# schem.net
KiCad netlist of a schematic drawn in EAGLE
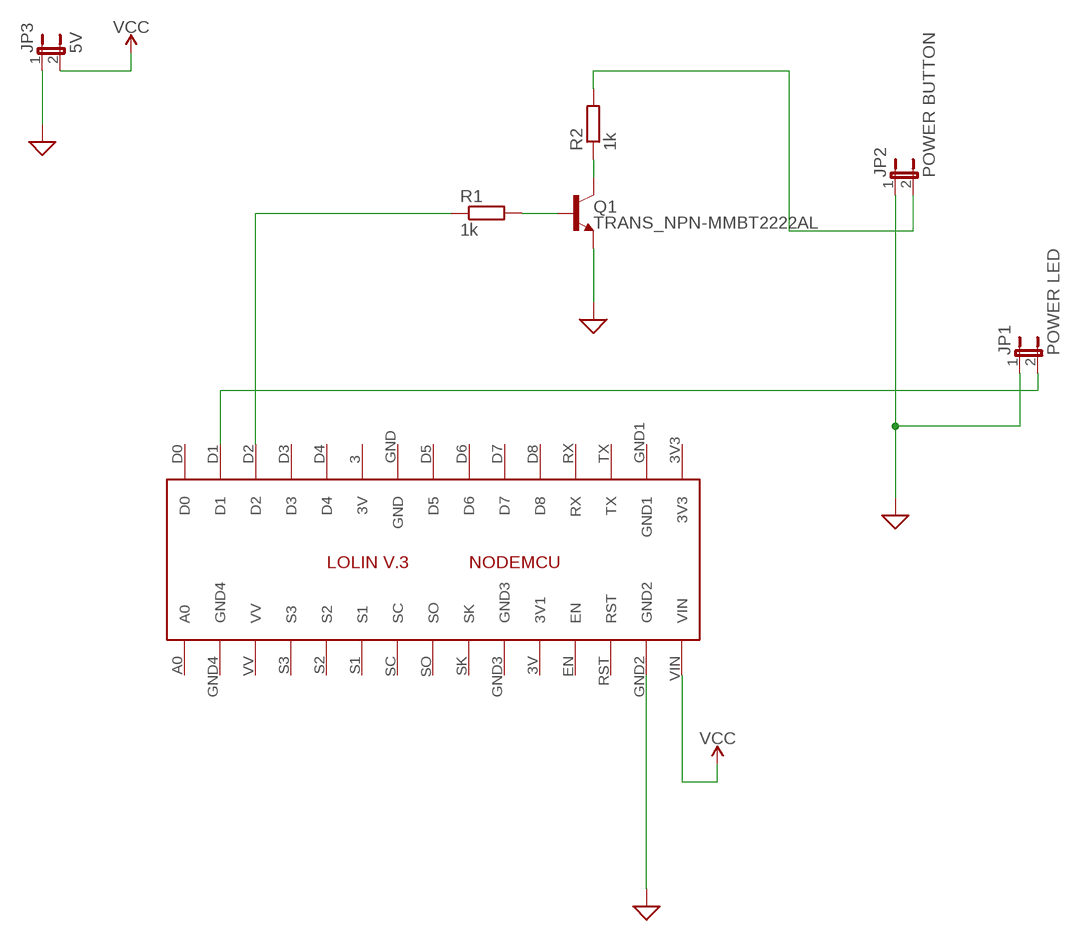
[diagram p0: schematic, sheet 1]

(export (version "E")
  (design (tool "Eeschema 10.0.6"))
  (components
    (comp (ref "IC1")
      (value "LOLINV3")
      (footprint "eagle-import:LOLINV3")
      (libsource (lib "eagle-import") (part "LOLINV3"))
    )
    (comp (ref "JP1")
      (value "POWER LED")
      (footprint "eagle-import:JP1")
      (libsource (lib "eagle-import") (part "JP1E"))
    )
    (comp (ref "JP2")
      (value "POWER BUTTON")
      (footprint "eagle-import:JP1")
      (libsource (lib "eagle-import") (part "JP1E"))
    )
    (comp (ref "JP3")
      (value "5V")
      (footprint "eagle-import:JP1")
      (libsource (lib "eagle-import") (part "JP1E"))
    )
    (comp (ref "Q1")
      (value "TRANS_NPN-MMBT2222AL")
      (footprint "eagle-import:SOT23-3")
      (libsource (lib "eagle-import") (part "TRANS_NPN-MMBT2222AL"))
    )
    (comp (ref "R1")
      (value "1k")
      (footprint "eagle-import:M0805")
      (libsource (lib "eagle-import") (part "R-EU_M0805"))
    )
    (comp (ref "R2")
      (value "1k")
      (footprint "eagle-import:M0805")
      (libsource (lib "eagle-import") (part "R-EU_M0805"))
    )
  )
  (nets
    (net (code "1") (name "Net-(IC1-PadD1)") (class "Default")
      (node (ref "IC1") (pin "D1") (pinfunction "D1_D1") (pintype "bidirectional"))
      (node (ref "JP1") (pin "2") (pinfunction "2_2") (pintype "passive"))
    )
    (net (code "2") (name "Net-(IC1-PadD2)") (class "Default")
      (node (ref "IC1") (pin "D2") (pinfunction "D2_D2") (pintype "bidirectional"))
      (node (ref "R1") (pin "1") (pinfunction "1_1") (pintype "passive"))
    )
    (net (code "3") (name "Net-(JP2-Pad2)") (class "Default")
      (node (ref "JP2") (pin "2") (pinfunction "2_2") (pintype "passive"))
      (node (ref "R2") (pin "2") (pinfunction "2_2") (pintype "passive"))
    )
    (net (code "4") (name "Net-(Q1-B)") (class "Default")
      (node (ref "Q1") (pin "1") (pinfunction "B_1") (pintype "passive"))
      (node (ref "R1") (pin "2") (pinfunction "2_2") (pintype "passive"))
    )
    (net (code "5") (name "Net-(Q1-C)") (class "Default")
      (node (ref "Q1") (pin "3") (pinfunction "C_3") (pintype "passive"))
      (node (ref "R2") (pin "1") (pinfunction "1_1") (pintype "passive"))
    )
    (net (code "6") (name "SUP") (class "Default")
      (node (ref "IC1") (pin "GND2") (pinfunction "GND2_GND2") (pintype "bidirectional"))
      (node (ref "JP1") (pin "1") (pinfunction "1_1") (pintype "passive"))
      (node (ref "JP2") (pin "1") (pinfunction "1_1") (pintype "passive"))
      (node (ref "JP3") (pin "1") (pinfunction "1_1") (pintype "passive"))
      (node (ref "Q1") (pin "2") (pinfunction "E_2") (pintype "passive"))
    )
    (net (code "7") (name "VCC") (class "Default")
      (node (ref "IC1") (pin "VIN") (pinfunction "VIN_VIN") (pintype "bidirectional"))
      (node (ref "JP3") (pin "2") (pinfunction "2_2") (pintype "passive"))
    )
    (net (code "8") (name "unconnected-(IC1-3V-Pad3)") (class "Default")
      (node (ref "IC1") (pin "3") (pinfunction "3V_3") (pintype "bidirectional"))
    )
    (net (code "9") (name "unconnected-(IC1-3V1-Pad3V)") (class "Default")
      (node (ref "IC1") (pin "3V") (pinfunction "3V1_3V") (pintype "bidirectional"))
    )
    (net (code "10") (name "unconnected-(IC1-Pad3V3)") (class "Default")
      (node (ref "IC1") (pin "3V3") (pinfunction "3V3_3V3") (pintype "bidirectional"))
    )
    (net (code "11") (name "unconnected-(IC1-PadA0)") (class "Default")
      (node (ref "IC1") (pin "A0") (pinfunction "A0_A0") (pintype "bidirectional"))
    )
    (net (code "12") (name "unconnected-(IC1-PadD0)") (class "Default")
      (node (ref "IC1") (pin "D0") (pinfunction "D0_D0") (pintype "bidirectional"))
    )
    (net (code "13") (name "unconnected-(IC1-PadD3)") (class "Default")
      (node (ref "IC1") (pin "D3") (pinfunction "D3_D3") (pintype "bidirectional"))
    )
    (net (code "14") (name "unconnected-(IC1-PadD4)") (class "Default")
      (node (ref "IC1") (pin "D4") (pinfunction "D4_D4") (pintype "bidirectional"))
    )
    (net (code "15") (name "unconnected-(IC1-PadD5)") (class "Default")
      (node (ref "IC1") (pin "D5") (pinfunction "D5_D5") (pintype "bidirectional"))
    )
    (net (code "16") (name "unconnected-(IC1-PadD6)") (class "Default")
      (node (ref "IC1") (pin "D6") (pinfunction "D6_D6") (pintype "bidirectional"))
    )
    (net (code "17") (name "unconnected-(IC1-PadD7)") (class "Default")
      (node (ref "IC1") (pin "D7") (pinfunction "D7_D7") (pintype "bidirectional"))
    )
    (net (code "18") (name "unconnected-(IC1-PadD8)") (class "Default")
      (node (ref "IC1") (pin "D8") (pinfunction "D8_D8") (pintype "bidirectional"))
    )
    (net (code "19") (name "unconnected-(IC1-PadEN)") (class "Default")
      (node (ref "IC1") (pin "EN") (pinfunction "EN_EN") (pintype "bidirectional"))
    )
    (net (code "20") (name "unconnected-(IC1-PadGND)") (class "Default")
      (node (ref "IC1") (pin "GND") (pinfunction "GND_GND") (pintype "bidirectional"))
    )
    (net (code "21") (name "unconnected-(IC1-PadGND1)") (class "Default")
      (node (ref "IC1") (pin "GND1") (pinfunction "GND1_GND1") (pintype "bidirectional"))
    )
    (net (code "22") (name "unconnected-(IC1-PadGND3)") (class "Default")
      (node (ref "IC1") (pin "GND3") (pinfunction "GND3_GND3") (pintype "bidirectional"))
    )
    (net (code "23") (name "unconnected-(IC1-PadGND4)") (class "Default")
      (node (ref "IC1") (pin "GND4") (pinfunction "GND4_GND4") (pintype "bidirectional"))
    )
    (net (code "24") (name "unconnected-(IC1-PadRST)") (class "Default")
      (node (ref "IC1") (pin "RST") (pinfunction "RST_RST") (pintype "bidirectional"))
    )
    (net (code "25") (name "unconnected-(IC1-PadRX)") (class "Default")
      (node (ref "IC1") (pin "RX") (pinfunction "RX_RX") (pintype "bidirectional"))
    )
    (net (code "26") (name "unconnected-(IC1-PadS1)") (class "Default")
      (node (ref "IC1") (pin "S1") (pinfunction "S1_S1") (pintype "bidirectional"))
    )
    (net (code "27") (name "unconnected-(IC1-PadS2)") (class "Default")
      (node (ref "IC1") (pin "S2") (pinfunction "S2_S2") (pintype "bidirectional"))
    )
    (net (code "28") (name "unconnected-(IC1-PadS3)") (class "Default")
      (node (ref "IC1") (pin "S3") (pinfunction "S3_S3") (pintype "bidirectional"))
    )
    (net (code "29") (name "unconnected-(IC1-PadSC)") (class "Default")
      (node (ref "IC1") (pin "SC") (pinfunction "SC_SC") (pintype "bidirectional"))
    )
    (net (code "30") (name "unconnected-(IC1-PadSK)") (class "Default")
      (node (ref "IC1") (pin "SK") (pinfunction "SK_SK") (pintype "bidirectional"))
    )
    (net (code "31") (name "unconnected-(IC1-PadSO)") (class "Default")
      (node (ref "IC1") (pin "SO") (pinfunction "SO_SO") (pintype "bidirectional"))
    )
    (net (code "32") (name "unconnected-(IC1-PadTX)") (class "Default")
      (node (ref "IC1") (pin "TX") (pinfunction "TX_TX") (pintype "bidirectional"))
    )
    (net (code "33") (name "unconnected-(IC1-PadVV)") (class "Default")
      (node (ref "IC1") (pin "VV") (pinfunction "VV_VV") (pintype "bidirectional"))
    )
  )
)
